# AlmosFinalMC.net
KiCad netlist of a schematic drawn in EAGLE
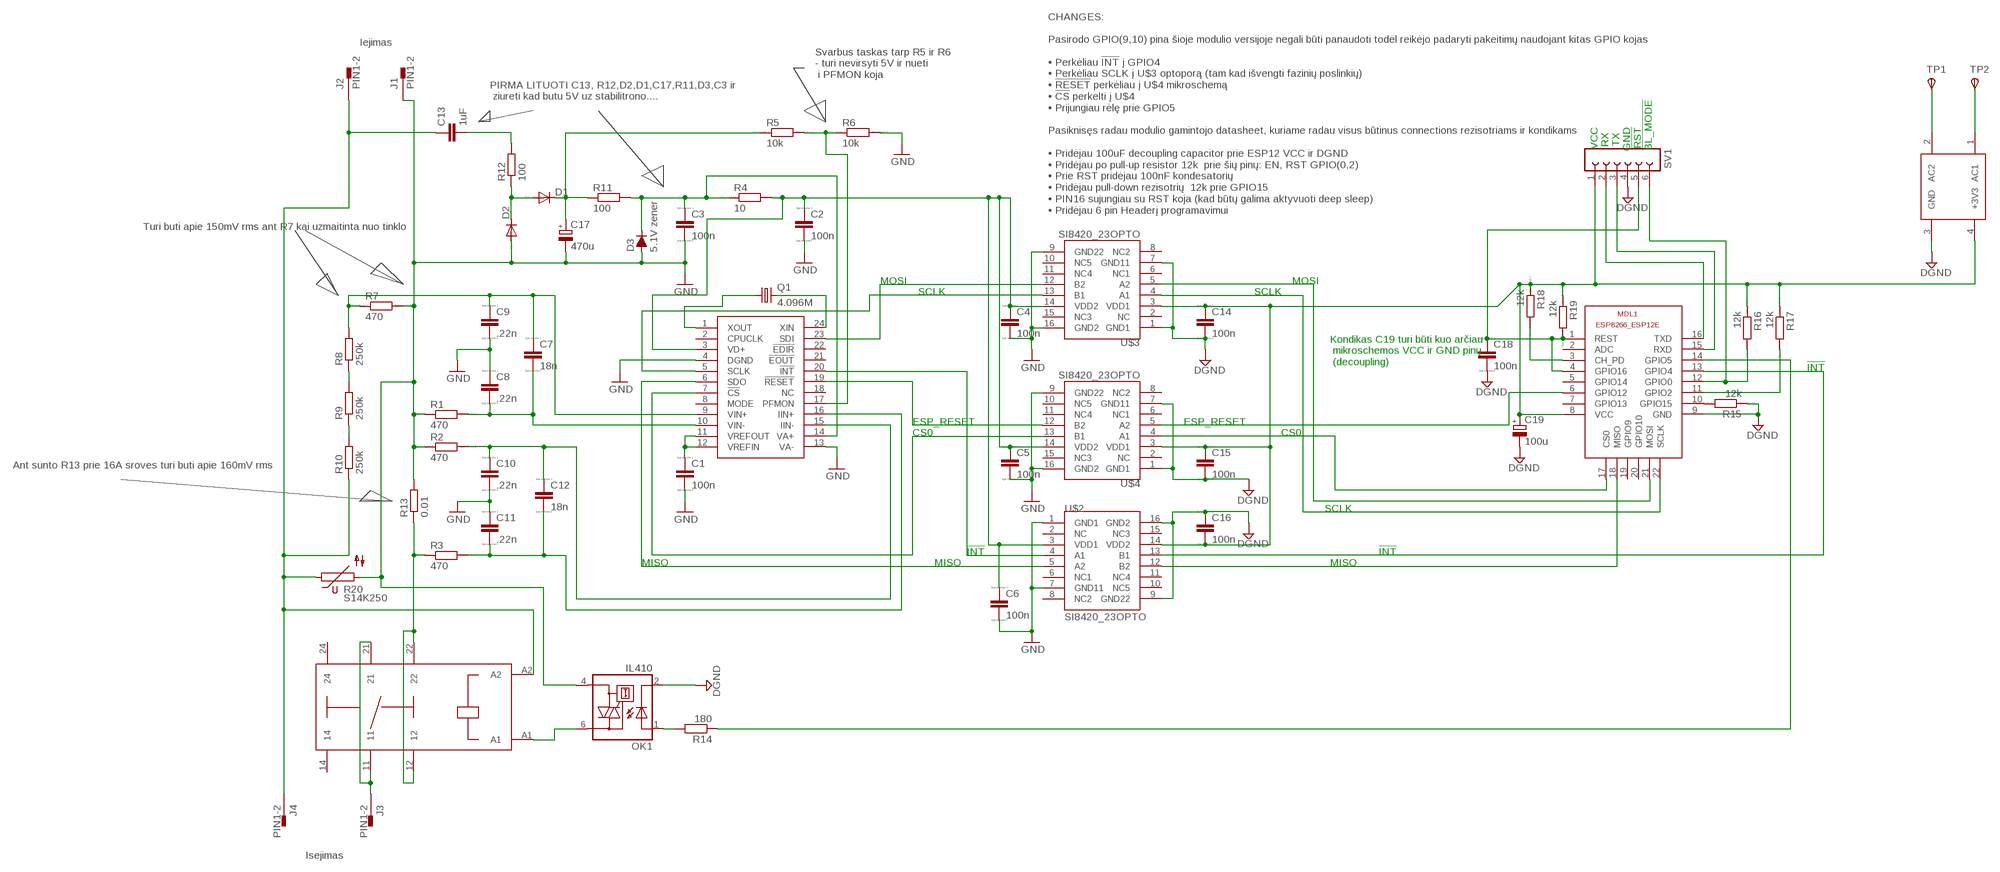
[diagram p0: schematic, sheet 1]

(export (version "E")
  (design (tool "Eeschema 10.0.6"))
  (components
    (comp (ref "C1")
      (value "100n")
      (footprint "eagle-import:C0805")
      (libsource (lib "eagle-import") (part "C"))
    )
    (comp (ref "C2")
      (value "100n")
      (footprint "eagle-import:C0805")
      (libsource (lib "eagle-import") (part "C"))
    )
    (comp (ref "C3")
      (value "100n")
      (footprint "eagle-import:C0805")
      (libsource (lib "eagle-import") (part "C"))
    )
    (comp (ref "C4")
      (value "100n")
      (footprint "eagle-import:C0805")
      (libsource (lib "eagle-import") (part "C"))
    )
    (comp (ref "C5")
      (value "100n")
      (footprint "eagle-import:C0805")
      (libsource (lib "eagle-import") (part "C"))
    )
    (comp (ref "C6")
      (value "100n")
      (footprint "eagle-import:C0805")
      (libsource (lib "eagle-import") (part "C"))
    )
    (comp (ref "C7")
      (value "18n")
      (footprint "eagle-import:C0805")
      (libsource (lib "eagle-import") (part "C"))
    )
    (comp (ref "C8")
      (value ".22n")
      (footprint "eagle-import:C0805")
      (libsource (lib "eagle-import") (part "C"))
    )
    (comp (ref "C9")
      (value ".22n")
      (footprint "eagle-import:C0805")
      (libsource (lib "eagle-import") (part "C"))
    )
    (comp (ref "C10")
      (value ".22n")
      (footprint "eagle-import:C0805")
      (libsource (lib "eagle-import") (part "C"))
    )
    (comp (ref "C11")
      (value ".22n")
      (footprint "eagle-import:C0805")
      (libsource (lib "eagle-import") (part "C"))
    )
    (comp (ref "C12")
      (value "18n")
      (footprint "eagle-import:C0805")
      (libsource (lib "eagle-import") (part "C"))
    )
    (comp (ref "C13")
      (value "1uF")
      (footprint "eagle-import:C225-113X268")
      (libsource (lib "eagle-import") (part "C-EU225-113X268"))
    )
    (comp (ref "C14")
      (value "100n")
      (footprint "eagle-import:C0805")
      (libsource (lib "eagle-import") (part "C"))
    )
    (comp (ref "C15")
      (value "100n")
      (footprint "eagle-import:C0805")
      (libsource (lib "eagle-import") (part "C"))
    )
    (comp (ref "C16")
      (value "100n")
      (footprint "eagle-import:C0805")
      (libsource (lib "eagle-import") (part "C"))
    )
    (comp (ref "C17")
      (value "470u")
      (footprint "eagle-import:PANASONIC_G")
      (libsource (lib "eagle-import") (part "CPOL-EUG"))
    )
    (comp (ref "C18")
      (value "100n")
      (footprint "eagle-import:C0805")
      (libsource (lib "eagle-import") (part "C"))
    )
    (comp (ref "C19")
      (value "100u")
      (footprint "eagle-import:PANASONIC_G")
      (libsource (lib "eagle-import") (part "CPOL-EUG"))
    )
    (comp (ref "D1")
      (value "DIODE-DO-214AC")
      (footprint "eagle-import:DO-214AC")
      (libsource (lib "eagle-import") (part "DIODE-DO-214AC"))
    )
    (comp (ref "D2")
      (value "DIODE-DO-214AC")
      (footprint "eagle-import:DO-214AC")
      (libsource (lib "eagle-import") (part "DIODE-DO-214AC"))
    )
    (comp (ref "D3")
      (value "5.1V zener")
      (footprint "eagle-import:SOD123")
      (libsource (lib "eagle-import") (part "D-FILL-SOD123"))
    )
    (comp (ref "J1")
      (value "PIN1-2")
      (footprint "eagle-import:62221")
      (fields (field (name "MF") "TYCO ELECTRONICS") (field (name "MPN") "62221-1"))
      (libsource (lib "eagle-import") (part "PIN1-2"))
    )
    (comp (ref "J2")
      (value "PIN1-2")
      (footprint "eagle-import:62221")
      (fields (field (name "MF") "TYCO ELECTRONICS") (field (name "MPN") "62221-1"))
      (libsource (lib "eagle-import") (part "PIN1-2"))
    )
    (comp (ref "J3")
      (value "PIN1-2")
      (footprint "eagle-import:62221")
      (fields (field (name "MF") "TYCO ELECTRONICS") (field (name "MPN") "62221-1"))
      (libsource (lib "eagle-import") (part "PIN1-2"))
    )
    (comp (ref "J4")
      (value "PIN1-2")
      (footprint "eagle-import:62221")
      (fields (field (name "MF") "TYCO ELECTRONICS") (field (name "MPN") "62221-1"))
      (libsource (lib "eagle-import") (part "PIN1-2"))
    )
    (comp (ref "MDL1")
      (value "ESP8266-12EESP8266-ESP12E")
      (footprint "eagle-import:ESP8266-ESP12E")
      (libsource (lib "eagle-import") (part "ESP8266-12EESP8266-ESP12E"))
    )
    (comp (ref "OK1")
      (value "IL410")
      (footprint "eagle-import:DIL06")
      (fields (field (name "MF") "VISHAY/TELEFUNKEN"))
      (libsource (lib "eagle-import") (part "IL410"))
    )
    (comp (ref "Q1")
      (value "4.096M")
      (footprint "eagle-import:HC49UP")
      (libsource (lib "eagle-import") (part "CRYSTALHC49UP"))
    )
    (comp (ref "R1")
      (value "470")
      (footprint "eagle-import:R0805")
      (libsource (lib "eagle-import") (part "R"))
    )
    (comp (ref "R2")
      (value "470")
      (footprint "eagle-import:R0805")
      (libsource (lib "eagle-import") (part "R"))
    )
    (comp (ref "R3")
      (value "470")
      (footprint "eagle-import:R0805")
      (libsource (lib "eagle-import") (part "R"))
    )
    (comp (ref "R4")
      (value "10")
      (footprint "eagle-import:R0805")
      (libsource (lib "eagle-import") (part "R"))
    )
    (comp (ref "R5")
      (value "10k")
      (footprint "eagle-import:R0805")
      (libsource (lib "eagle-import") (part "R"))
    )
    (comp (ref "R6")
      (value "10k")
      (footprint "eagle-import:R0805")
      (libsource (lib "eagle-import") (part "R"))
    )
    (comp (ref "R7")
      (value "470")
      (footprint "eagle-import:R0805")
      (libsource (lib "eagle-import") (part "R"))
    )
    (comp (ref "R8")
      (value "250k")
      (footprint "eagle-import:0204_5")
      (libsource (lib "eagle-import") (part "R-EU_0204/5"))
    )
    (comp (ref "R9")
      (value "250k")
      (footprint "eagle-import:0204_5")
      (libsource (lib "eagle-import") (part "R-EU_0204/5"))
    )
    (comp (ref "R10")
      (value "250k")
      (footprint "eagle-import:0204_5")
      (libsource (lib "eagle-import") (part "R-EU_0204/5"))
    )
    (comp (ref "R11")
      (value "100")
      (footprint "eagle-import:0207_5V")
      (libsource (lib "eagle-import") (part "R-EU_0207/5V"))
    )
    (comp (ref "R12")
      (value "100")
      (footprint "eagle-import:0309_10")
      (libsource (lib "eagle-import") (part "R-EU_0309/10"))
    )
    (comp (ref "R13")
      (value "0.01")
      (footprint "eagle-import:RDH_15")
      (libsource (lib "eagle-import") (part "R-EU_RDH/15"))
    )
    (comp (ref "R14")
      (value "180")
      (footprint "eagle-import:R0805")
      (libsource (lib "eagle-import") (part "R-EU_R0805"))
    )
    (comp (ref "R15")
      (value "12k")
      (footprint "eagle-import:R0805")
      (libsource (lib "eagle-import") (part "R"))
    )
    (comp (ref "R16")
      (value "12k")
      (footprint "eagle-import:R0805")
      (libsource (lib "eagle-import") (part "R"))
    )
    (comp (ref "R17")
      (value "12k")
      (footprint "eagle-import:R0805")
      (libsource (lib "eagle-import") (part "R"))
    )
    (comp (ref "R18")
      (value "12k")
      (footprint "eagle-import:R0805")
      (libsource (lib "eagle-import") (part "R"))
    )
    (comp (ref "R19")
      (value "12k")
      (footprint "eagle-import:R0805")
      (libsource (lib "eagle-import") (part "R"))
    )
    (comp (ref "R20")
      (value "S14K250")
      (footprint "eagle-import:S14K250")
      (libsource (lib "eagle-import") (part "S14K250"))
    )
    (comp (ref "SV1")
      (value "FE06-1")
      (footprint "eagle-import:FE06")
      (libsource (lib "eagle-import") (part "FE06-1"))
    )
    (comp (ref "TP1")
      (value "TPSPAD1-20Y")
      (footprint "eagle-import:P1-20Y")
      (libsource (lib "eagle-import") (part "TPSPAD1-20Y"))
    )
    (comp (ref "TP2")
      (value "TPSPAD1-20Y")
      (footprint "eagle-import:P1-20Y")
      (libsource (lib "eagle-import") (part "TPSPAD1-20Y"))
    )
    (comp (ref "U$1")
      (value "CS5460A")
      (footprint "eagle-import:SSOP24")
      (libsource (lib "eagle-import") (part "CS5460A"))
    )
    (comp (ref "U$2")
      (value "SI8420_23OPTO")
      (footprint "eagle-import:SI8420-SOIC8WB")
      (libsource (lib "eagle-import") (part "SI8420_23OPTO"))
    )
    (comp (ref "U$3")
      (value "SI8420_23OPTO")
      (footprint "eagle-import:SI8420-SOIC8WB")
      (libsource (lib "eagle-import") (part "SI8420_23OPTO"))
    )
    (comp (ref "U$4")
      (value "SI8420_23OPTO")
      (footprint "eagle-import:SI8420-SOIC8WB")
      (libsource (lib "eagle-import") (part "SI8420_23OPTO"))
    )
    (comp (ref "U$5")
      (value "RAC02")
      (footprint "eagle-import:RAC02")
      (libsource (lib "eagle-import") (part "RAC02"))
    )
    (comp (ref "U$6")
      (value "FINDER40-61")
      (footprint "eagle-import:FINDER40-61")
      (libsource (lib "eagle-import") (part "FINDER40-61"))
    )
  )
  (nets
    (net (code "1") (name "DGND") (class "Default")
      (node (ref "C14") (pin "2") (pinfunction "2_2") (pintype "passive"))
      (node (ref "C15") (pin "2") (pinfunction "2_2") (pintype "passive"))
      (node (ref "C16") (pin "1") (pinfunction "1_1") (pintype "passive"))
      (node (ref "C18") (pin "2") (pinfunction "2_2") (pintype "passive"))
      (node (ref "C19") (pin "-") (pinfunction "-_-") (pintype "passive"))
      (node (ref "MDL1") (pin "9") (pinfunction "GND_9") (pintype "bidirectional"))
      (node (ref "OK1") (pin "2") (pinfunction "C_2") (pintype "passive"))
      (node (ref "R15") (pin "1") (pinfunction "1_1") (pintype "passive"))
      (node (ref "SV1") (pin "4") (pinfunction "4_4") (pintype "passive"))
      (node (ref "U$2") (pin "16") (pinfunction "GND2_16") (pintype "bidirectional"))
      (node (ref "U$2") (pin "9") (pinfunction "GND22_9") (pintype "bidirectional"))
      (node (ref "U$3") (pin "1") (pinfunction "GND1_1") (pintype "bidirectional"))
      (node (ref "U$3") (pin "7") (pinfunction "GND11_7") (pintype "bidirectional"))
      (node (ref "U$4") (pin "1") (pinfunction "GND1_1") (pintype "bidirectional"))
      (node (ref "U$4") (pin "7") (pinfunction "GND11_7") (pintype "bidirectional"))
      (node (ref "U$5") (pin "3") (pinfunction "GND_3") (pintype "bidirectional"))
    )
    (net (code "2") (name "GND") (class "Default")
      (node (ref "C1") (pin "2") (pinfunction "2_2") (pintype "passive"))
      (node (ref "C10") (pin "2") (pinfunction "2_2") (pintype "passive"))
      (node (ref "C11") (pin "1") (pinfunction "1_1") (pintype "passive"))
      (node (ref "C17") (pin "-") (pinfunction "-_-") (pintype "passive"))
      (node (ref "C2") (pin "2") (pinfunction "2_2") (pintype "passive"))
      (node (ref "C3") (pin "2") (pinfunction "2_2") (pintype "passive"))
      (node (ref "C4") (pin "2") (pinfunction "2_2") (pintype "passive"))
      (node (ref "C5") (pin "2") (pinfunction "2_2") (pintype "passive"))
      (node (ref "C6") (pin "2") (pinfunction "2_2") (pintype "passive"))
      (node (ref "C8") (pin "1") (pinfunction "1_1") (pintype "passive"))
      (node (ref "C9") (pin "2") (pinfunction "2_2") (pintype "passive"))
      (node (ref "D2") (pin "A") (pinfunction "A_A") (pintype "passive"))
      (node (ref "D3") (pin "2") (pinfunction "A_2") (pintype "passive"))
      (node (ref "J1") (pin "1") (pinfunction "1_1") (pintype "passive"))
      (node (ref "OK1") (pin "4") (pinfunction "A1_4") (pintype "passive"))
      (node (ref "R1") (pin "1") (pinfunction "1_1") (pintype "passive"))
      (node (ref "R13") (pin "2") (pinfunction "2_2") (pintype "passive"))
      (node (ref "R2") (pin "1") (pinfunction "1_1") (pintype "passive"))
      (node (ref "R20") (pin "2") (pinfunction "2_2") (pintype "passive"))
      (node (ref "R6") (pin "2") (pinfunction "2_2") (pintype "passive"))
      (node (ref "R7") (pin "2") (pinfunction "2_2") (pintype "passive"))
      (node (ref "U$1") (pin "13") (pinfunction "VA-_13") (pintype "bidirectional"))
      (node (ref "U$1") (pin "4") (pinfunction "DGND_4") (pintype "bidirectional"))
      (node (ref "U$2") (pin "1") (pinfunction "GND1_1") (pintype "bidirectional"))
      (node (ref "U$2") (pin "7") (pinfunction "GND11_7") (pintype "bidirectional"))
      (node (ref "U$3") (pin "16") (pinfunction "GND2_16") (pintype "bidirectional"))
      (node (ref "U$3") (pin "9") (pinfunction "GND22_9") (pintype "bidirectional"))
      (node (ref "U$4") (pin "16") (pinfunction "GND2_16") (pintype "bidirectional"))
      (node (ref "U$4") (pin "9") (pinfunction "GND22_9") (pintype "bidirectional"))
    )
    (net (code "3") (name "Net-(C13-Pad1)") (class "Default")
      (node (ref "C13") (pin "1") (pinfunction "1_1") (pintype "passive"))
      (node (ref "J2") (pin "1") (pinfunction "1_1") (pintype "passive"))
      (node (ref "J4") (pin "1") (pinfunction "1_1") (pintype "passive"))
      (node (ref "R10") (pin "1") (pinfunction "1_1") (pintype "passive"))
      (node (ref "R20") (pin "1") (pinfunction "1_1") (pintype "passive"))
      (node (ref "U$6") (pin "A2") (pinfunction "A2_A2") (pintype "bidirectional"))
    )
    (net (code "4") (name "Net-(C13-Pad2)") (class "Default")
      (node (ref "C13") (pin "2") (pinfunction "2_2") (pintype "passive"))
      (node (ref "R12") (pin "2") (pinfunction "2_2") (pintype "passive"))
    )
    (net (code "5") (name "Net-(C17-Pad+)") (class "Default")
      (node (ref "C17") (pin "+") (pinfunction "+_+") (pintype "passive"))
      (node (ref "D1") (pin "C") (pinfunction "C_C") (pintype "passive"))
      (node (ref "R11") (pin "1") (pinfunction "1_1") (pintype "passive"))
      (node (ref "R5") (pin "1") (pinfunction "1_1") (pintype "passive"))
    )
    (net (code "6") (name "Net-(D1-PadA)") (class "Default")
      (node (ref "D1") (pin "A") (pinfunction "A_A") (pintype "passive"))
      (node (ref "D2") (pin "C") (pinfunction "C_C") (pintype "passive"))
      (node (ref "R12") (pin "1") (pinfunction "1_1") (pintype "passive"))
    )
    (net (code "7") (name "Net-(D3-C)") (class "Default")
      (node (ref "C3") (pin "1") (pinfunction "1_1") (pintype "passive"))
      (node (ref "D3") (pin "1") (pinfunction "C_1") (pintype "passive"))
      (node (ref "R11") (pin "2") (pinfunction "2_2") (pintype "passive"))
      (node (ref "R4") (pin "1") (pinfunction "1_1") (pintype "passive"))
      (node (ref "U$1") (pin "14") (pinfunction "VA+_14") (pintype "bidirectional"))
    )
    (net (code "8") (name "Net-(J3-Pad1)") (class "Default")
      (node (ref "J3") (pin "1") (pinfunction "1_1") (pintype "passive"))
      (node (ref "U$6") (pin "11") (pinfunction "11_11") (pintype "bidirectional"))
      (node (ref "U$6") (pin "21") (pinfunction "21_21") (pintype "bidirectional"))
    )
    (net (code "9") (name "Net-(MDL1-CH_PD)") (class "Default")
      (node (ref "MDL1") (pin "3") (pinfunction "CH_PD_3") (pintype "bidirectional"))
      (node (ref "R18") (pin "2") (pinfunction "2_2") (pintype "passive"))
    )
    (net (code "10") (name "Net-(MDL1-CS0)") (class "Default")
      (node (ref "MDL1") (pin "17") (pinfunction "CS0_17") (pintype "bidirectional"))
      (node (ref "U$4") (pin "4") (pinfunction "A1_4") (pintype "bidirectional"))
    )
    (net (code "11") (name "Net-(MDL1-GPIO0)") (class "Default")
      (node (ref "MDL1") (pin "12") (pinfunction "GPIO0_12") (pintype "bidirectional"))
      (node (ref "R16") (pin "2") (pinfunction "2_2") (pintype "passive"))
      (node (ref "SV1") (pin "6") (pinfunction "6_6") (pintype "passive"))
    )
    (net (code "12") (name "Net-(MDL1-GPIO2)") (class "Default")
      (node (ref "MDL1") (pin "11") (pinfunction "GPIO2_11") (pintype "bidirectional"))
      (node (ref "R17") (pin "2") (pinfunction "2_2") (pintype "passive"))
    )
    (net (code "13") (name "Net-(MDL1-GPIO4)") (class "Default")
      (node (ref "MDL1") (pin "13") (pinfunction "GPIO4_13") (pintype "bidirectional"))
      (node (ref "U$2") (pin "13") (pinfunction "B1_13") (pintype "bidirectional"))
    )
    (net (code "14") (name "Net-(MDL1-GPIO5)") (class "Default")
      (node (ref "MDL1") (pin "14") (pinfunction "GPIO5_14") (pintype "bidirectional"))
      (node (ref "R14") (pin "1") (pinfunction "1_1") (pintype "passive"))
    )
    (net (code "15") (name "Net-(MDL1-GPIO12)") (class "Default")
      (node (ref "MDL1") (pin "6") (pinfunction "GPIO12_6") (pintype "bidirectional"))
      (node (ref "U$4") (pin "5") (pinfunction "A2_5") (pintype "bidirectional"))
    )
    (net (code "16") (name "Net-(MDL1-GPIO15)") (class "Default")
      (node (ref "MDL1") (pin "10") (pinfunction "GPIO15_10") (pintype "bidirectional"))
      (node (ref "R15") (pin "2") (pinfunction "2_2") (pintype "passive"))
    )
    (net (code "17") (name "Net-(MDL1-GPIO16)") (class "Default")
      (node (ref "C18") (pin "1") (pinfunction "1_1") (pintype "passive"))
      (node (ref "MDL1") (pin "1") (pinfunction "REST_1") (pintype "bidirectional"))
      (node (ref "MDL1") (pin "4") (pinfunction "GPIO16_4") (pintype "bidirectional"))
      (node (ref "R19") (pin "2") (pinfunction "2_2") (pintype "passive"))
      (node (ref "SV1") (pin "5") (pinfunction "5_5") (pintype "passive"))
    )
    (net (code "18") (name "Net-(MDL1-MISO)") (class "Default")
      (node (ref "MDL1") (pin "18") (pinfunction "MISO_18") (pintype "bidirectional"))
      (node (ref "U$2") (pin "12") (pinfunction "B2_12") (pintype "bidirectional"))
    )
    (net (code "19") (name "Net-(MDL1-MOSI)") (class "Default")
      (node (ref "MDL1") (pin "21") (pinfunction "MOSI_21") (pintype "bidirectional"))
      (node (ref "U$3") (pin "5") (pinfunction "A2_5") (pintype "bidirectional"))
    )
    (net (code "20") (name "Net-(MDL1-RXD)") (class "Default")
      (node (ref "MDL1") (pin "15") (pinfunction "RXD_15") (pintype "bidirectional"))
      (node (ref "SV1") (pin "3") (pinfunction "3_3") (pintype "passive"))
    )
    (net (code "21") (name "Net-(MDL1-SCLK)") (class "Default")
      (node (ref "MDL1") (pin "22") (pinfunction "SCLK_22") (pintype "bidirectional"))
      (node (ref "U$3") (pin "4") (pinfunction "A1_4") (pintype "bidirectional"))
    )
    (net (code "22") (name "Net-(MDL1-TXD)") (class "Default")
      (node (ref "MDL1") (pin "16") (pinfunction "TXD_16") (pintype "bidirectional"))
      (node (ref "SV1") (pin "2") (pinfunction "2_2") (pintype "passive"))
    )
    (net (code "23") (name "Net-(MDL1-VCC)") (class "Default")
      (node (ref "C14") (pin "1") (pinfunction "1_1") (pintype "passive"))
      (node (ref "C15") (pin "1") (pinfunction "1_1") (pintype "passive"))
      (node (ref "C16") (pin "2") (pinfunction "2_2") (pintype "passive"))
      (node (ref "C19") (pin "+") (pinfunction "+_+") (pintype "passive"))
      (node (ref "MDL1") (pin "8") (pinfunction "VCC_8") (pintype "bidirectional"))
      (node (ref "R16") (pin "1") (pinfunction "1_1") (pintype "passive"))
      (node (ref "R17") (pin "1") (pinfunction "1_1") (pintype "passive"))
      (node (ref "R18") (pin "1") (pinfunction "1_1") (pintype "passive"))
      (node (ref "R19") (pin "1") (pinfunction "1_1") (pintype "passive"))
      (node (ref "SV1") (pin "1") (pinfunction "1_1") (pintype "passive"))
      (node (ref "U$2") (pin "14") (pinfunction "VDD2_14") (pintype "bidirectional"))
      (node (ref "U$3") (pin "3") (pinfunction "VDD1_3") (pintype "bidirectional"))
      (node (ref "U$4") (pin "3") (pinfunction "VDD1_3") (pintype "bidirectional"))
      (node (ref "U$5") (pin "4") (pinfunction "+3V3_4") (pintype "bidirectional"))
    )
    (net (code "24") (name "Net-(OK1-A)") (class "Default")
      (node (ref "OK1") (pin "1") (pinfunction "A_1") (pintype "passive"))
      (node (ref "R14") (pin "2") (pinfunction "2_2") (pintype "passive"))
    )
    (net (code "25") (name "Net-(OK1-A2)") (class "Default")
      (node (ref "OK1") (pin "6") (pinfunction "A2_6") (pintype "passive"))
      (node (ref "U$6") (pin "A1") (pinfunction "A1_A1") (pintype "bidirectional"))
    )
    (net (code "26") (name "Net-(R8-Pad1)") (class "Default")
      (node (ref "R8") (pin "1") (pinfunction "1_1") (pintype "passive"))
      (node (ref "R9") (pin "2") (pinfunction "2_2") (pintype "passive"))
    )
    (net (code "27") (name "Net-(R10-Pad2)") (class "Default")
      (node (ref "R10") (pin "2") (pinfunction "2_2") (pintype "passive"))
      (node (ref "R9") (pin "1") (pinfunction "1_1") (pintype "passive"))
    )
    (net (code "28") (name "Net-(R13-Pad1)") (class "Default")
      (node (ref "R13") (pin "1") (pinfunction "1_1") (pintype "passive"))
      (node (ref "R3") (pin "1") (pinfunction "1_1") (pintype "passive"))
      (node (ref "U$6") (pin "12") (pinfunction "12_12") (pintype "bidirectional"))
      (node (ref "U$6") (pin "22") (pinfunction "22_22") (pintype "bidirectional"))
    )
    (net (code "29") (name "Net-(TP1-PP)") (class "Default")
      (node (ref "TP1") (pin "TP") (pinfunction "PP_TP") (pintype "input"))
      (node (ref "U$5") (pin "2") (pinfunction "AC2_2") (pintype "bidirectional"))
    )
    (net (code "30") (name "Net-(TP2-PP)") (class "Default")
      (node (ref "TP2") (pin "TP") (pinfunction "PP_TP") (pintype "input"))
      (node (ref "U$5") (pin "1") (pinfunction "AC1_1") (pintype "bidirectional"))
    )
    (net (code "31") (name "Net-(U$1-IIN+)") (class "Default")
      (node (ref "C11") (pin "2") (pinfunction "2_2") (pintype "passive"))
      (node (ref "C12") (pin "2") (pinfunction "2_2") (pintype "passive"))
      (node (ref "R3") (pin "2") (pinfunction "2_2") (pintype "passive"))
      (node (ref "U$1") (pin "16") (pinfunction "IIN+_16") (pintype "bidirectional"))
    )
    (net (code "32") (name "Net-(U$1-IIN-)") (class "Default")
      (node (ref "C10") (pin "1") (pinfunction "1_1") (pintype "passive"))
      (node (ref "C12") (pin "1") (pinfunction "1_1") (pintype "passive"))
      (node (ref "R2") (pin "2") (pinfunction "2_2") (pintype "passive"))
      (node (ref "U$1") (pin "15") (pinfunction "IIN-_15") (pintype "bidirectional"))
    )
    (net (code "33") (name "Net-(U$1-PFMON)") (class "Default")
      (node (ref "R5") (pin "2") (pinfunction "2_2") (pintype "passive"))
      (node (ref "R6") (pin "1") (pinfunction "1_1") (pintype "passive"))
      (node (ref "U$1") (pin "17") (pinfunction "PFMON_17") (pintype "bidirectional"))
    )
    (net (code "34") (name "Net-(U$1-SCLK)") (class "Default")
      (node (ref "U$1") (pin "5") (pinfunction "SCLK_5") (pintype "bidirectional"))
      (node (ref "U$3") (pin "13") (pinfunction "B1_13") (pintype "bidirectional"))
    )
    (net (code "35") (name "Net-(U$1-SDI)") (class "Default")
      (node (ref "U$1") (pin "23") (pinfunction "SDI_23") (pintype "bidirectional"))
      (node (ref "U$3") (pin "12") (pinfunction "B2_12") (pintype "bidirectional"))
    )
    (net (code "36") (name "Net-(U$1-SDO)") (class "Default")
      (node (ref "U$1") (pin "6") (pinfunction "SDO_6") (pintype "bidirectional"))
      (node (ref "U$2") (pin "5") (pinfunction "A2_5") (pintype "bidirectional"))
    )
    (net (code "37") (name "Net-(U$1-VD+)") (class "Default")
      (node (ref "C2") (pin "1") (pinfunction "1_1") (pintype "passive"))
      (node (ref "C4") (pin "1") (pinfunction "1_1") (pintype "passive"))
      (node (ref "C5") (pin "1") (pinfunction "1_1") (pintype "passive"))
      (node (ref "C6") (pin "1") (pinfunction "1_1") (pintype "passive"))
      (node (ref "R4") (pin "2") (pinfunction "2_2") (pintype "passive"))
      (node (ref "U$1") (pin "3") (pinfunction "VD+_3") (pintype "bidirectional"))
      (node (ref "U$2") (pin "3") (pinfunction "VDD1_3") (pintype "bidirectional"))
      (node (ref "U$3") (pin "14") (pinfunction "VDD2_14") (pintype "bidirectional"))
      (node (ref "U$4") (pin "14") (pinfunction "VDD2_14") (pintype "bidirectional"))
    )
    (net (code "38") (name "Net-(U$1-VIN+)") (class "Default")
      (node (ref "C7") (pin "1") (pinfunction "1_1") (pintype "passive"))
      (node (ref "C9") (pin "1") (pinfunction "1_1") (pintype "passive"))
      (node (ref "R7") (pin "1") (pinfunction "1_1") (pintype "passive"))
      (node (ref "R8") (pin "2") (pinfunction "2_2") (pintype "passive"))
      (node (ref "U$1") (pin "9") (pinfunction "VIN+_9") (pintype "bidirectional"))
    )
    (net (code "39") (name "Net-(U$1-VIN-)") (class "Default")
      (node (ref "C7") (pin "2") (pinfunction "2_2") (pintype "passive"))
      (node (ref "C8") (pin "2") (pinfunction "2_2") (pintype "passive"))
      (node (ref "R1") (pin "2") (pinfunction "2_2") (pintype "passive"))
      (node (ref "U$1") (pin "10") (pinfunction "VIN-_10") (pintype "bidirectional"))
    )
    (net (code "40") (name "Net-(U$1-VREFIN)") (class "Default")
      (node (ref "C1") (pin "1") (pinfunction "1_1") (pintype "passive"))
      (node (ref "U$1") (pin "11") (pinfunction "VREFOUT_11") (pintype "bidirectional"))
      (node (ref "U$1") (pin "12") (pinfunction "VREFIN_12") (pintype "bidirectional"))
    )
    (net (code "41") (name "Net-(U$1-XIN)") (class "Default")
      (node (ref "Q1") (pin "2") (pinfunction "2_2") (pintype "passive"))
      (node (ref "U$1") (pin "24") (pinfunction "XIN_24") (pintype "bidirectional"))
    )
    (net (code "42") (name "Net-(U$1-XOUT)") (class "Default")
      (node (ref "Q1") (pin "1") (pinfunction "1_1") (pintype "passive"))
      (node (ref "U$1") (pin "1") (pinfunction "XOUT_1") (pintype "bidirectional"))
    )
    (net (code "43") (name "Net-(U$1-~{CS})") (class "Default")
      (node (ref "U$1") (pin "7") (pinfunction "~{CS}_7") (pintype "bidirectional"))
      (node (ref "U$4") (pin "13") (pinfunction "B1_13") (pintype "bidirectional"))
    )
    (net (code "44") (name "Net-(U$1-~{INT})") (class "Default")
      (node (ref "U$1") (pin "20") (pinfunction "~{INT}_20") (pintype "bidirectional"))
      (node (ref "U$2") (pin "4") (pinfunction "A1_4") (pintype "bidirectional"))
    )
    (net (code "45") (name "Net-(U$1-~{RESET})") (class "Default")
      (node (ref "U$1") (pin "19") (pinfunction "~{RESET}_19") (pintype "bidirectional"))
      (node (ref "U$4") (pin "12") (pinfunction "B2_12") (pintype "bidirectional"))
    )
    (net (code "46") (name "unconnected-(MDL1-ADC-Pad2)") (class "Default")
      (node (ref "MDL1") (pin "2") (pinfunction "ADC_2") (pintype "bidirectional"))
    )
    (net (code "47") (name "unconnected-(MDL1-GPIO9-Pad19)") (class "Default")
      (node (ref "MDL1") (pin "19") (pinfunction "GPIO9_19") (pintype "bidirectional"))
    )
    (net (code "48") (name "unconnected-(MDL1-GPIO10-Pad20)") (class "Default")
      (node (ref "MDL1") (pin "20") (pinfunction "GPIO10_20") (pintype "bidirectional"))
    )
    (net (code "49") (name "unconnected-(MDL1-GPIO13-Pad7)") (class "Default")
      (node (ref "MDL1") (pin "7") (pinfunction "GPIO13_7") (pintype "bidirectional"))
    )
    (net (code "50") (name "unconnected-(MDL1-GPIO14-Pad5)") (class "Default")
      (node (ref "MDL1") (pin "5") (pinfunction "GPIO14_5") (pintype "bidirectional"))
    )
    (net (code "51") (name "unconnected-(U$1-CPUCLK-Pad2)") (class "Default")
      (node (ref "U$1") (pin "2") (pinfunction "CPUCLK_2") (pintype "bidirectional"))
    )
    (net (code "52") (name "unconnected-(U$1-MODE-Pad8)") (class "Default")
      (node (ref "U$1") (pin "8") (pinfunction "MODE_8") (pintype "bidirectional"))
    )
    (net (code "53") (name "unconnected-(U$1-NC-Pad18)") (class "Default")
      (node (ref "U$1") (pin "18") (pinfunction "NC_18") (pintype "bidirectional"))
    )
    (net (code "54") (name "unconnected-(U$1-~{EDIR}-Pad22)") (class "Default")
      (node (ref "U$1") (pin "22") (pinfunction "~{EDIR}_22") (pintype "bidirectional"))
    )
    (net (code "55") (name "unconnected-(U$1-~{EOUT}-Pad21)") (class "Default")
      (node (ref "U$1") (pin "21") (pinfunction "~{EOUT}_21") (pintype "bidirectional"))
    )
    (net (code "56") (name "unconnected-(U$2-NC-Pad2)") (class "Default")
      (node (ref "U$2") (pin "2") (pinfunction "NC_2") (pintype "no_connect"))
    )
    (net (code "57") (name "unconnected-(U$2-NC1-Pad6)") (class "Default")
      (node (ref "U$2") (pin "6") (pinfunction "NC1_6") (pintype "bidirectional"))
    )
    (net (code "58") (name "unconnected-(U$2-NC2-Pad8)") (class "Default")
      (node (ref "U$2") (pin "8") (pinfunction "NC2_8") (pintype "bidirectional"))
    )
    (net (code "59") (name "unconnected-(U$2-NC3-Pad15)") (class "Default")
      (node (ref "U$2") (pin "15") (pinfunction "NC3_15") (pintype "bidirectional"))
    )
    (net (code "60") (name "unconnected-(U$2-NC4-Pad11)") (class "Default")
      (node (ref "U$2") (pin "11") (pinfunction "NC4_11") (pintype "bidirectional"))
    )
    (net (code "61") (name "unconnected-(U$2-NC5-Pad10)") (class "Default")
      (node (ref "U$2") (pin "10") (pinfunction "NC5_10") (pintype "bidirectional"))
    )
    (net (code "62") (name "unconnected-(U$3-NC-Pad2)") (class "Default")
      (node (ref "U$3") (pin "2") (pinfunction "NC_2") (pintype "no_connect"))
    )
    (net (code "63") (name "unconnected-(U$3-NC1-Pad6)") (class "Default")
      (node (ref "U$3") (pin "6") (pinfunction "NC1_6") (pintype "bidirectional"))
    )
    (net (code "64") (name "unconnected-(U$3-NC2-Pad8)") (class "Default")
      (node (ref "U$3") (pin "8") (pinfunction "NC2_8") (pintype "bidirectional"))
    )
    (net (code "65") (name "unconnected-(U$3-NC3-Pad15)") (class "Default")
      (node (ref "U$3") (pin "15") (pinfunction "NC3_15") (pintype "bidirectional"))
    )
    (net (code "66") (name "unconnected-(U$3-NC4-Pad11)") (class "Default")
      (node (ref "U$3") (pin "11") (pinfunction "NC4_11") (pintype "bidirectional"))
    )
    (net (code "67") (name "unconnected-(U$3-NC5-Pad10)") (class "Default")
      (node (ref "U$3") (pin "10") (pinfunction "NC5_10") (pintype "bidirectional"))
    )
    (net (code "68") (name "unconnected-(U$4-NC-Pad2)") (class "Default")
      (node (ref "U$4") (pin "2") (pinfunction "NC_2") (pintype "no_connect"))
    )
    (net (code "69") (name "unconnected-(U$4-NC1-Pad6)") (class "Default")
      (node (ref "U$4") (pin "6") (pinfunction "NC1_6") (pintype "bidirectional"))
    )
    (net (code "70") (name "unconnected-(U$4-NC2-Pad8)") (class "Default")
      (node (ref "U$4") (pin "8") (pinfunction "NC2_8") (pintype "bidirectional"))
    )
    (net (code "71") (name "unconnected-(U$4-NC3-Pad15)") (class "Default")
      (node (ref "U$4") (pin "15") (pinfunction "NC3_15") (pintype "bidirectional"))
    )
    (net (code "72") (name "unconnected-(U$4-NC4-Pad11)") (class "Default")
      (node (ref "U$4") (pin "11") (pinfunction "NC4_11") (pintype "bidirectional"))
    )
    (net (code "73") (name "unconnected-(U$4-NC5-Pad10)") (class "Default")
      (node (ref "U$4") (pin "10") (pinfunction "NC5_10") (pintype "bidirectional"))
    )
    (net (code "74") (name "unconnected-(U$6-Pad14)") (class "Default")
      (node (ref "U$6") (pin "14") (pinfunction "14_14") (pintype "bidirectional"))
    )
    (net (code "75") (name "unconnected-(U$6-Pad24)") (class "Default")
      (node (ref "U$6") (pin "24") (pinfunction "24_24") (pintype "bidirectional"))
    )
  )
)
